# tdt_maleToMale.net
KiCad netlist of a schematic drawn in EAGLE
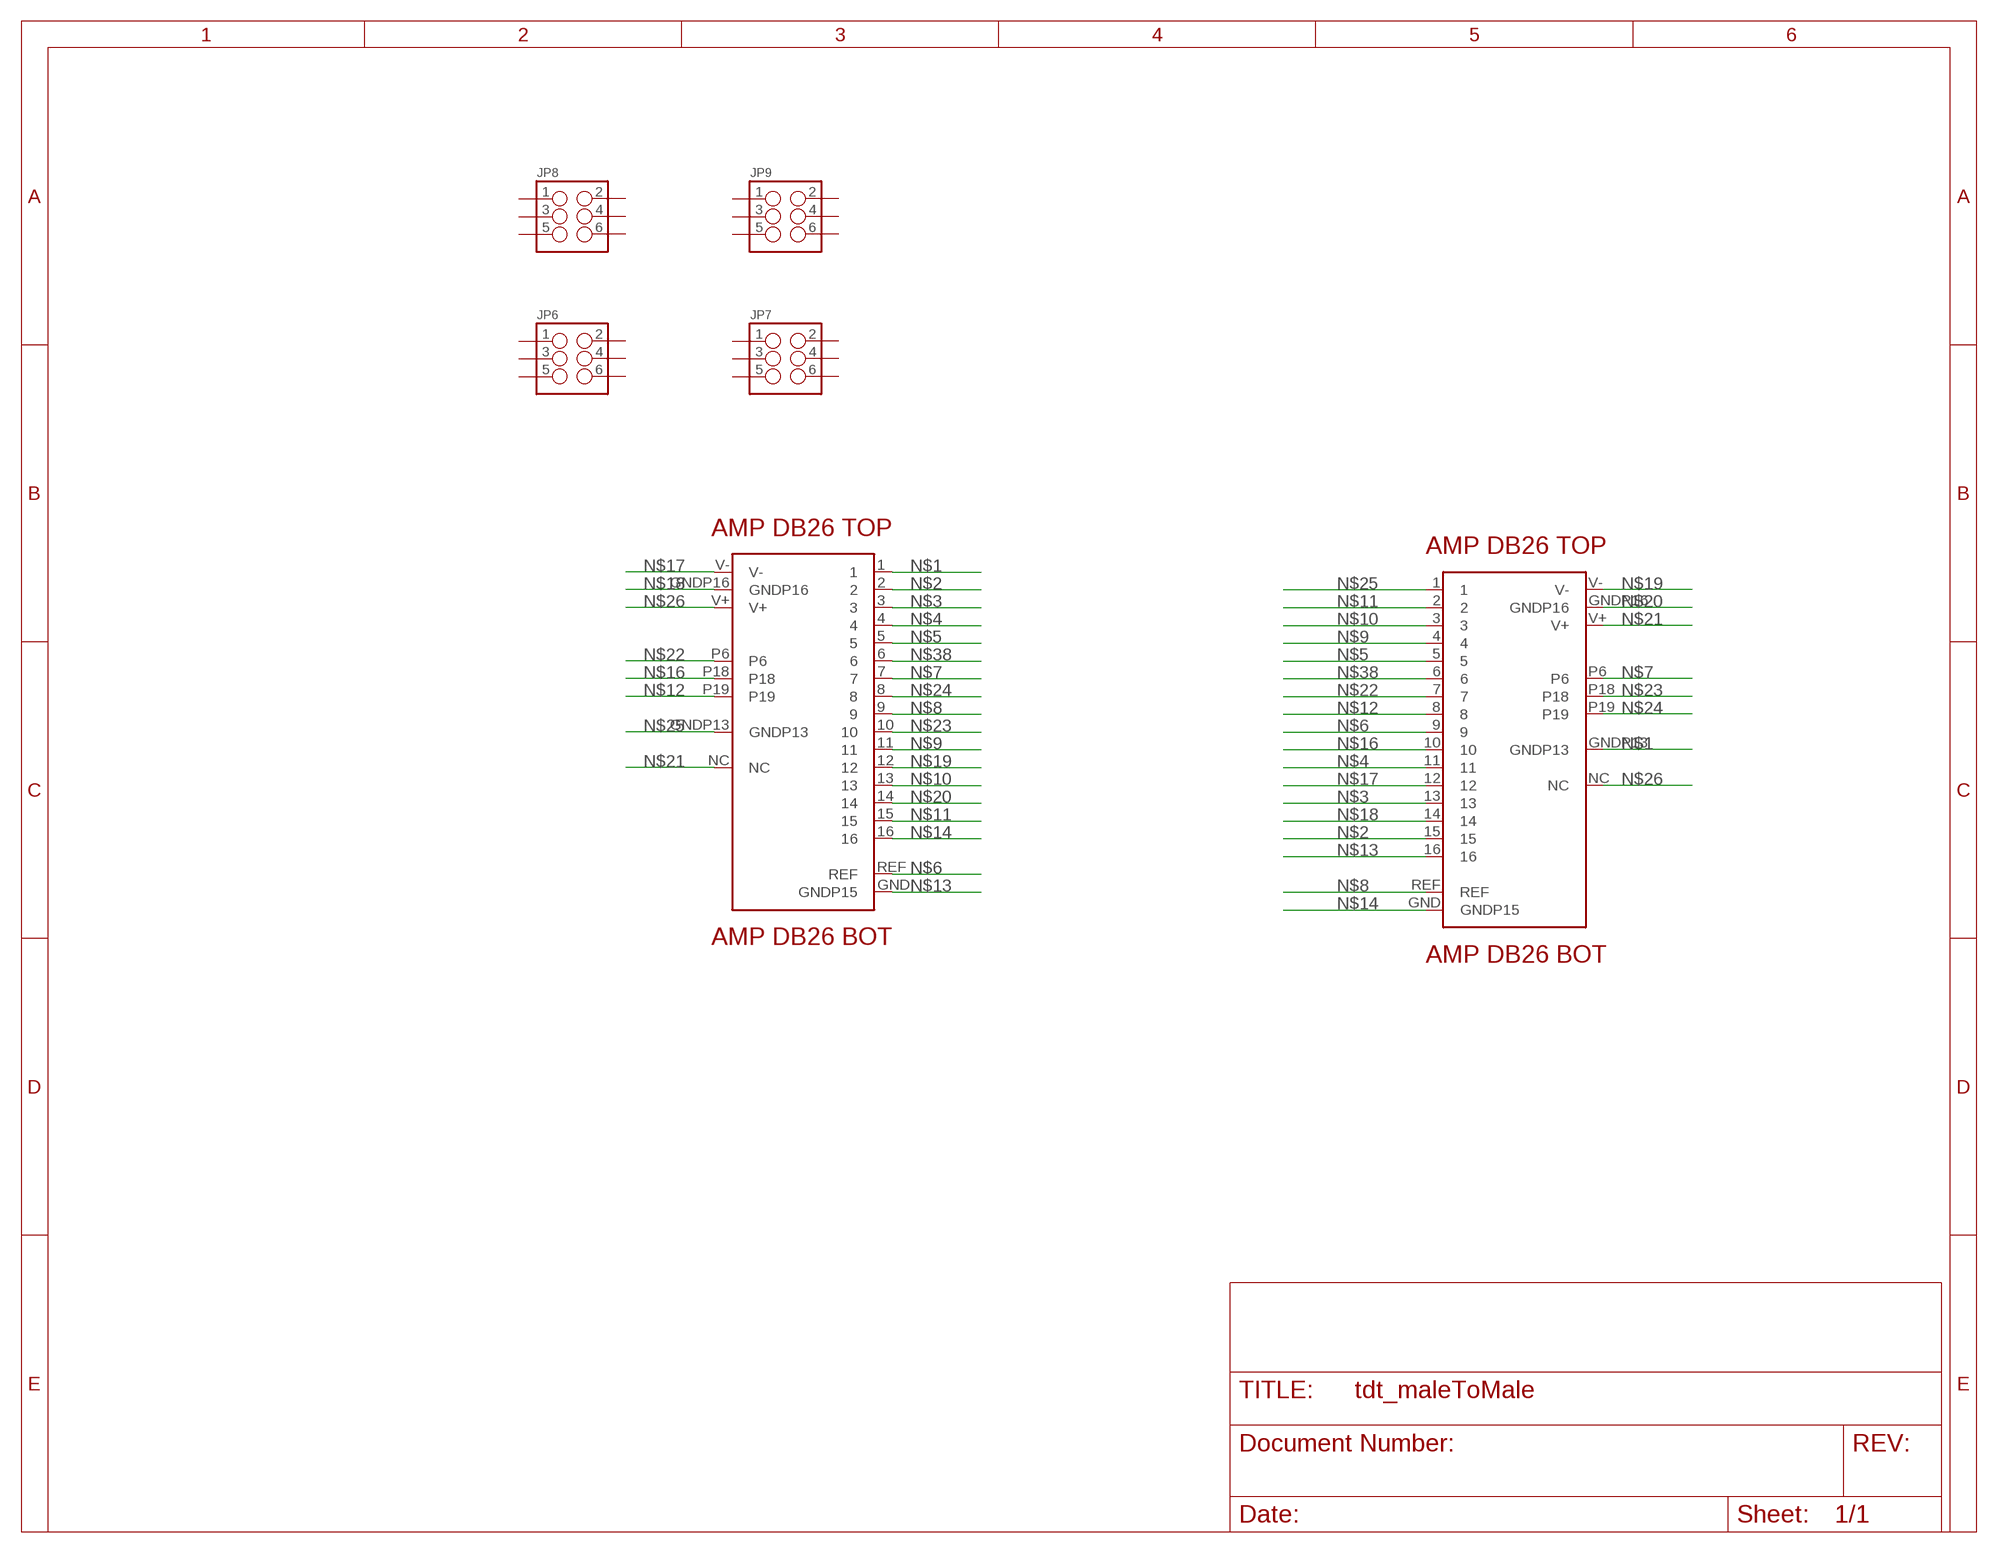
[diagram p0: schematic, sheet 1]

(export (version "E")
  (design (tool "Eeschema 10.0.6"))
  (components
    (comp (ref "JP6")
      (value "M03X22X3_SILK_MALE_PTH")
      (footprint "eagle-import:2X3")
      (libsource (lib "eagle-import") (part "M03X22X3_SILK_MALE_PTH"))
    )
    (comp (ref "JP7")
      (value "M03X22X3_SILK_MALE_PTH")
      (footprint "eagle-import:2X3")
      (libsource (lib "eagle-import") (part "M03X22X3_SILK_MALE_PTH"))
    )
    (comp (ref "JP8")
      (value "M03X22X3_SILK_MALE_PTH")
      (footprint "eagle-import:2X3")
      (libsource (lib "eagle-import") (part "M03X22X3_SILK_MALE_PTH"))
    )
    (comp (ref "JP9")
      (value "M03X22X3_SILK_MALE_PTH")
      (footprint "eagle-import:2X3")
      (libsource (lib "eagle-import") (part "M03X22X3_SILK_MALE_PTH"))
    )
    (comp (ref "U$1")
      (value "DB26-MALE-BOT")
      (footprint "eagle-import:DB26-MALE-BOT")
      (libsource (lib "eagle-import") (part "DB26-MALE-BOT"))
    )
    (comp (ref "U$2")
      (value "DB26-MALE-TOP")
      (footprint "eagle-import:DB26-MALE-TOP")
      (libsource (lib "eagle-import") (part "DB26-MALE-TOP"))
    )
    (comp (ref "U$3")
      (value "DB26-MALE-TOP")
      (footprint "eagle-import:DB26-MALE-TOP")
      (libsource (lib "eagle-import") (part "DB26-MALE-TOP"))
    )
    (comp (ref "U$4")
      (value "DB26-MALE-BOT")
      (footprint "eagle-import:DB26-MALE-BOT")
      (libsource (lib "eagle-import") (part "DB26-MALE-BOT"))
    )
  )
  (nets
    (net (code "1") (name "/N$1") (class "Default")
      (node (ref "U$2") (pin "1") (pinfunction "1_1") (pintype "bidirectional"))
      (node (ref "U$3") (pin "GNDP13") (pinfunction "GNDP13_GNDP13") (pintype "bidirectional"))
    )
    (net (code "2") (name "/N$2") (class "Default")
      (node (ref "U$2") (pin "2") (pinfunction "2_2") (pintype "bidirectional"))
      (node (ref "U$3") (pin "15") (pinfunction "15_15") (pintype "bidirectional"))
    )
    (net (code "3") (name "/N$3") (class "Default")
      (node (ref "U$2") (pin "3") (pinfunction "3_3") (pintype "bidirectional"))
      (node (ref "U$3") (pin "13") (pinfunction "13_13") (pintype "bidirectional"))
    )
    (net (code "4") (name "/N$4") (class "Default")
      (node (ref "U$2") (pin "4") (pinfunction "4_4") (pintype "bidirectional"))
      (node (ref "U$3") (pin "11") (pinfunction "11_11") (pintype "bidirectional"))
    )
    (net (code "5") (name "/N$5") (class "Default")
      (node (ref "U$2") (pin "5") (pinfunction "5_5") (pintype "bidirectional"))
      (node (ref "U$3") (pin "5") (pinfunction "5_5") (pintype "bidirectional"))
    )
    (net (code "6") (name "/N$6") (class "Default")
      (node (ref "U$2") (pin "REF") (pinfunction "REF_REF") (pintype "bidirectional"))
      (node (ref "U$3") (pin "9") (pinfunction "9_9") (pintype "bidirectional"))
    )
    (net (code "7") (name "/N$7") (class "Default")
      (node (ref "U$2") (pin "7") (pinfunction "7_7") (pintype "bidirectional"))
      (node (ref "U$3") (pin "P6") (pinfunction "P6_P6") (pintype "bidirectional"))
    )
    (net (code "8") (name "/N$8") (class "Default")
      (node (ref "U$2") (pin "9") (pinfunction "9_9") (pintype "bidirectional"))
      (node (ref "U$3") (pin "REF") (pinfunction "REF_REF") (pintype "bidirectional"))
    )
    (net (code "9") (name "/N$9") (class "Default")
      (node (ref "U$2") (pin "11") (pinfunction "11_11") (pintype "bidirectional"))
      (node (ref "U$3") (pin "4") (pinfunction "4_4") (pintype "bidirectional"))
    )
    (net (code "10") (name "/N$10") (class "Default")
      (node (ref "U$2") (pin "13") (pinfunction "13_13") (pintype "bidirectional"))
      (node (ref "U$3") (pin "3") (pinfunction "3_3") (pintype "bidirectional"))
    )
    (net (code "11") (name "/N$11") (class "Default")
      (node (ref "U$2") (pin "15") (pinfunction "15_15") (pintype "bidirectional"))
      (node (ref "U$3") (pin "2") (pinfunction "2_2") (pintype "bidirectional"))
    )
    (net (code "12") (name "/N$12") (class "Default")
      (node (ref "U$1") (pin "P19") (pinfunction "P19_P19") (pintype "bidirectional"))
      (node (ref "U$4") (pin "8") (pinfunction "8_8") (pintype "bidirectional"))
    )
    (net (code "13") (name "/N$13") (class "Default")
      (node (ref "U$1") (pin "GND") (pinfunction "GNDP15_GND") (pintype "bidirectional"))
      (node (ref "U$4") (pin "16") (pinfunction "16_16") (pintype "bidirectional"))
    )
    (net (code "14") (name "/N$14") (class "Default")
      (node (ref "U$1") (pin "16") (pinfunction "16_16") (pintype "bidirectional"))
      (node (ref "U$4") (pin "GND") (pinfunction "GNDP15_GND") (pintype "bidirectional"))
    )
    (net (code "15") (name "/N$16") (class "Default")
      (node (ref "U$1") (pin "P18") (pinfunction "P18_P18") (pintype "bidirectional"))
      (node (ref "U$4") (pin "10") (pinfunction "10_10") (pintype "bidirectional"))
    )
    (net (code "16") (name "/N$17") (class "Default")
      (node (ref "U$1") (pin "V-") (pinfunction "V-_V-") (pintype "bidirectional"))
      (node (ref "U$4") (pin "12") (pinfunction "12_12") (pintype "bidirectional"))
    )
    (net (code "17") (name "/N$18") (class "Default")
      (node (ref "U$1") (pin "GNDP16") (pinfunction "GNDP16_GNDP16") (pintype "bidirectional"))
      (node (ref "U$4") (pin "14") (pinfunction "14_14") (pintype "bidirectional"))
    )
    (net (code "18") (name "/N$19") (class "Default")
      (node (ref "U$1") (pin "12") (pinfunction "12_12") (pintype "bidirectional"))
      (node (ref "U$4") (pin "V-") (pinfunction "V-_V-") (pintype "bidirectional"))
    )
    (net (code "19") (name "/N$20") (class "Default")
      (node (ref "U$1") (pin "14") (pinfunction "14_14") (pintype "bidirectional"))
      (node (ref "U$4") (pin "GNDP16") (pinfunction "GNDP16_GNDP16") (pintype "bidirectional"))
    )
    (net (code "20") (name "/N$21") (class "Default")
      (node (ref "U$1") (pin "NC") (pinfunction "NC_NC") (pintype "bidirectional"))
      (node (ref "U$4") (pin "V+") (pinfunction "V+_V+") (pintype "bidirectional"))
    )
    (net (code "21") (name "/N$22") (class "Default")
      (node (ref "U$2") (pin "P6") (pinfunction "P6_P6") (pintype "bidirectional"))
      (node (ref "U$3") (pin "7") (pinfunction "7_7") (pintype "bidirectional"))
    )
    (net (code "22") (name "/N$23") (class "Default")
      (node (ref "U$1") (pin "10") (pinfunction "10_10") (pintype "bidirectional"))
      (node (ref "U$4") (pin "P18") (pinfunction "P18_P18") (pintype "bidirectional"))
    )
    (net (code "23") (name "/N$24") (class "Default")
      (node (ref "U$1") (pin "8") (pinfunction "8_8") (pintype "bidirectional"))
      (node (ref "U$4") (pin "P19") (pinfunction "P19_P19") (pintype "bidirectional"))
    )
    (net (code "24") (name "/N$25") (class "Default")
      (node (ref "U$2") (pin "GNDP13") (pinfunction "GNDP13_GNDP13") (pintype "bidirectional"))
      (node (ref "U$3") (pin "1") (pinfunction "1_1") (pintype "bidirectional"))
    )
    (net (code "25") (name "/N$26") (class "Default")
      (node (ref "U$1") (pin "V+") (pinfunction "V+_V+") (pintype "bidirectional"))
      (node (ref "U$4") (pin "NC") (pinfunction "NC_NC") (pintype "bidirectional"))
    )
    (net (code "26") (name "/N$38") (class "Default")
      (node (ref "U$1") (pin "6") (pinfunction "6_6") (pintype "bidirectional"))
      (node (ref "U$4") (pin "6") (pinfunction "6_6") (pintype "bidirectional"))
    )
    (net (code "27") (name "unconnected-(JP6-Pad1)") (class "Default")
      (node (ref "JP6") (pin "1") (pinfunction "1_1") (pintype "bidirectional"))
    )
    (net (code "28") (name "unconnected-(JP6-Pad2)") (class "Default")
      (node (ref "JP6") (pin "2") (pinfunction "2_2") (pintype "bidirectional"))
    )
    (net (code "29") (name "unconnected-(JP6-Pad3)") (class "Default")
      (node (ref "JP6") (pin "3") (pinfunction "3_3") (pintype "bidirectional"))
    )
    (net (code "30") (name "unconnected-(JP6-Pad4)") (class "Default")
      (node (ref "JP6") (pin "4") (pinfunction "4_4") (pintype "bidirectional"))
    )
    (net (code "31") (name "unconnected-(JP6-Pad5)") (class "Default")
      (node (ref "JP6") (pin "5") (pinfunction "5_5") (pintype "bidirectional"))
    )
    (net (code "32") (name "unconnected-(JP6-Pad6)") (class "Default")
      (node (ref "JP6") (pin "6") (pinfunction "6_6") (pintype "bidirectional"))
    )
    (net (code "33") (name "unconnected-(JP7-Pad1)") (class "Default")
      (node (ref "JP7") (pin "1") (pinfunction "1_1") (pintype "bidirectional"))
    )
    (net (code "34") (name "unconnected-(JP7-Pad2)") (class "Default")
      (node (ref "JP7") (pin "2") (pinfunction "2_2") (pintype "bidirectional"))
    )
    (net (code "35") (name "unconnected-(JP7-Pad3)") (class "Default")
      (node (ref "JP7") (pin "3") (pinfunction "3_3") (pintype "bidirectional"))
    )
    (net (code "36") (name "unconnected-(JP7-Pad4)") (class "Default")
      (node (ref "JP7") (pin "4") (pinfunction "4_4") (pintype "bidirectional"))
    )
    (net (code "37") (name "unconnected-(JP7-Pad5)") (class "Default")
      (node (ref "JP7") (pin "5") (pinfunction "5_5") (pintype "bidirectional"))
    )
    (net (code "38") (name "unconnected-(JP7-Pad6)") (class "Default")
      (node (ref "JP7") (pin "6") (pinfunction "6_6") (pintype "bidirectional"))
    )
    (net (code "39") (name "unconnected-(JP8-Pad1)") (class "Default")
      (node (ref "JP8") (pin "1") (pinfunction "1_1") (pintype "bidirectional"))
    )
    (net (code "40") (name "unconnected-(JP8-Pad2)") (class "Default")
      (node (ref "JP8") (pin "2") (pinfunction "2_2") (pintype "bidirectional"))
    )
    (net (code "41") (name "unconnected-(JP8-Pad3)") (class "Default")
      (node (ref "JP8") (pin "3") (pinfunction "3_3") (pintype "bidirectional"))
    )
    (net (code "42") (name "unconnected-(JP8-Pad4)") (class "Default")
      (node (ref "JP8") (pin "4") (pinfunction "4_4") (pintype "bidirectional"))
    )
    (net (code "43") (name "unconnected-(JP8-Pad5)") (class "Default")
      (node (ref "JP8") (pin "5") (pinfunction "5_5") (pintype "bidirectional"))
    )
    (net (code "44") (name "unconnected-(JP8-Pad6)") (class "Default")
      (node (ref "JP8") (pin "6") (pinfunction "6_6") (pintype "bidirectional"))
    )
    (net (code "45") (name "unconnected-(JP9-Pad1)") (class "Default")
      (node (ref "JP9") (pin "1") (pinfunction "1_1") (pintype "bidirectional"))
    )
    (net (code "46") (name "unconnected-(JP9-Pad2)") (class "Default")
      (node (ref "JP9") (pin "2") (pinfunction "2_2") (pintype "bidirectional"))
    )
    (net (code "47") (name "unconnected-(JP9-Pad3)") (class "Default")
      (node (ref "JP9") (pin "3") (pinfunction "3_3") (pintype "bidirectional"))
    )
    (net (code "48") (name "unconnected-(JP9-Pad4)") (class "Default")
      (node (ref "JP9") (pin "4") (pinfunction "4_4") (pintype "bidirectional"))
    )
    (net (code "49") (name "unconnected-(JP9-Pad5)") (class "Default")
      (node (ref "JP9") (pin "5") (pinfunction "5_5") (pintype "bidirectional"))
    )
    (net (code "50") (name "unconnected-(JP9-Pad6)") (class "Default")
      (node (ref "JP9") (pin "6") (pinfunction "6_6") (pintype "bidirectional"))
    )
  )
)
